# small_analyzer.net
KiCad netlist of a schematic drawn in EAGLE
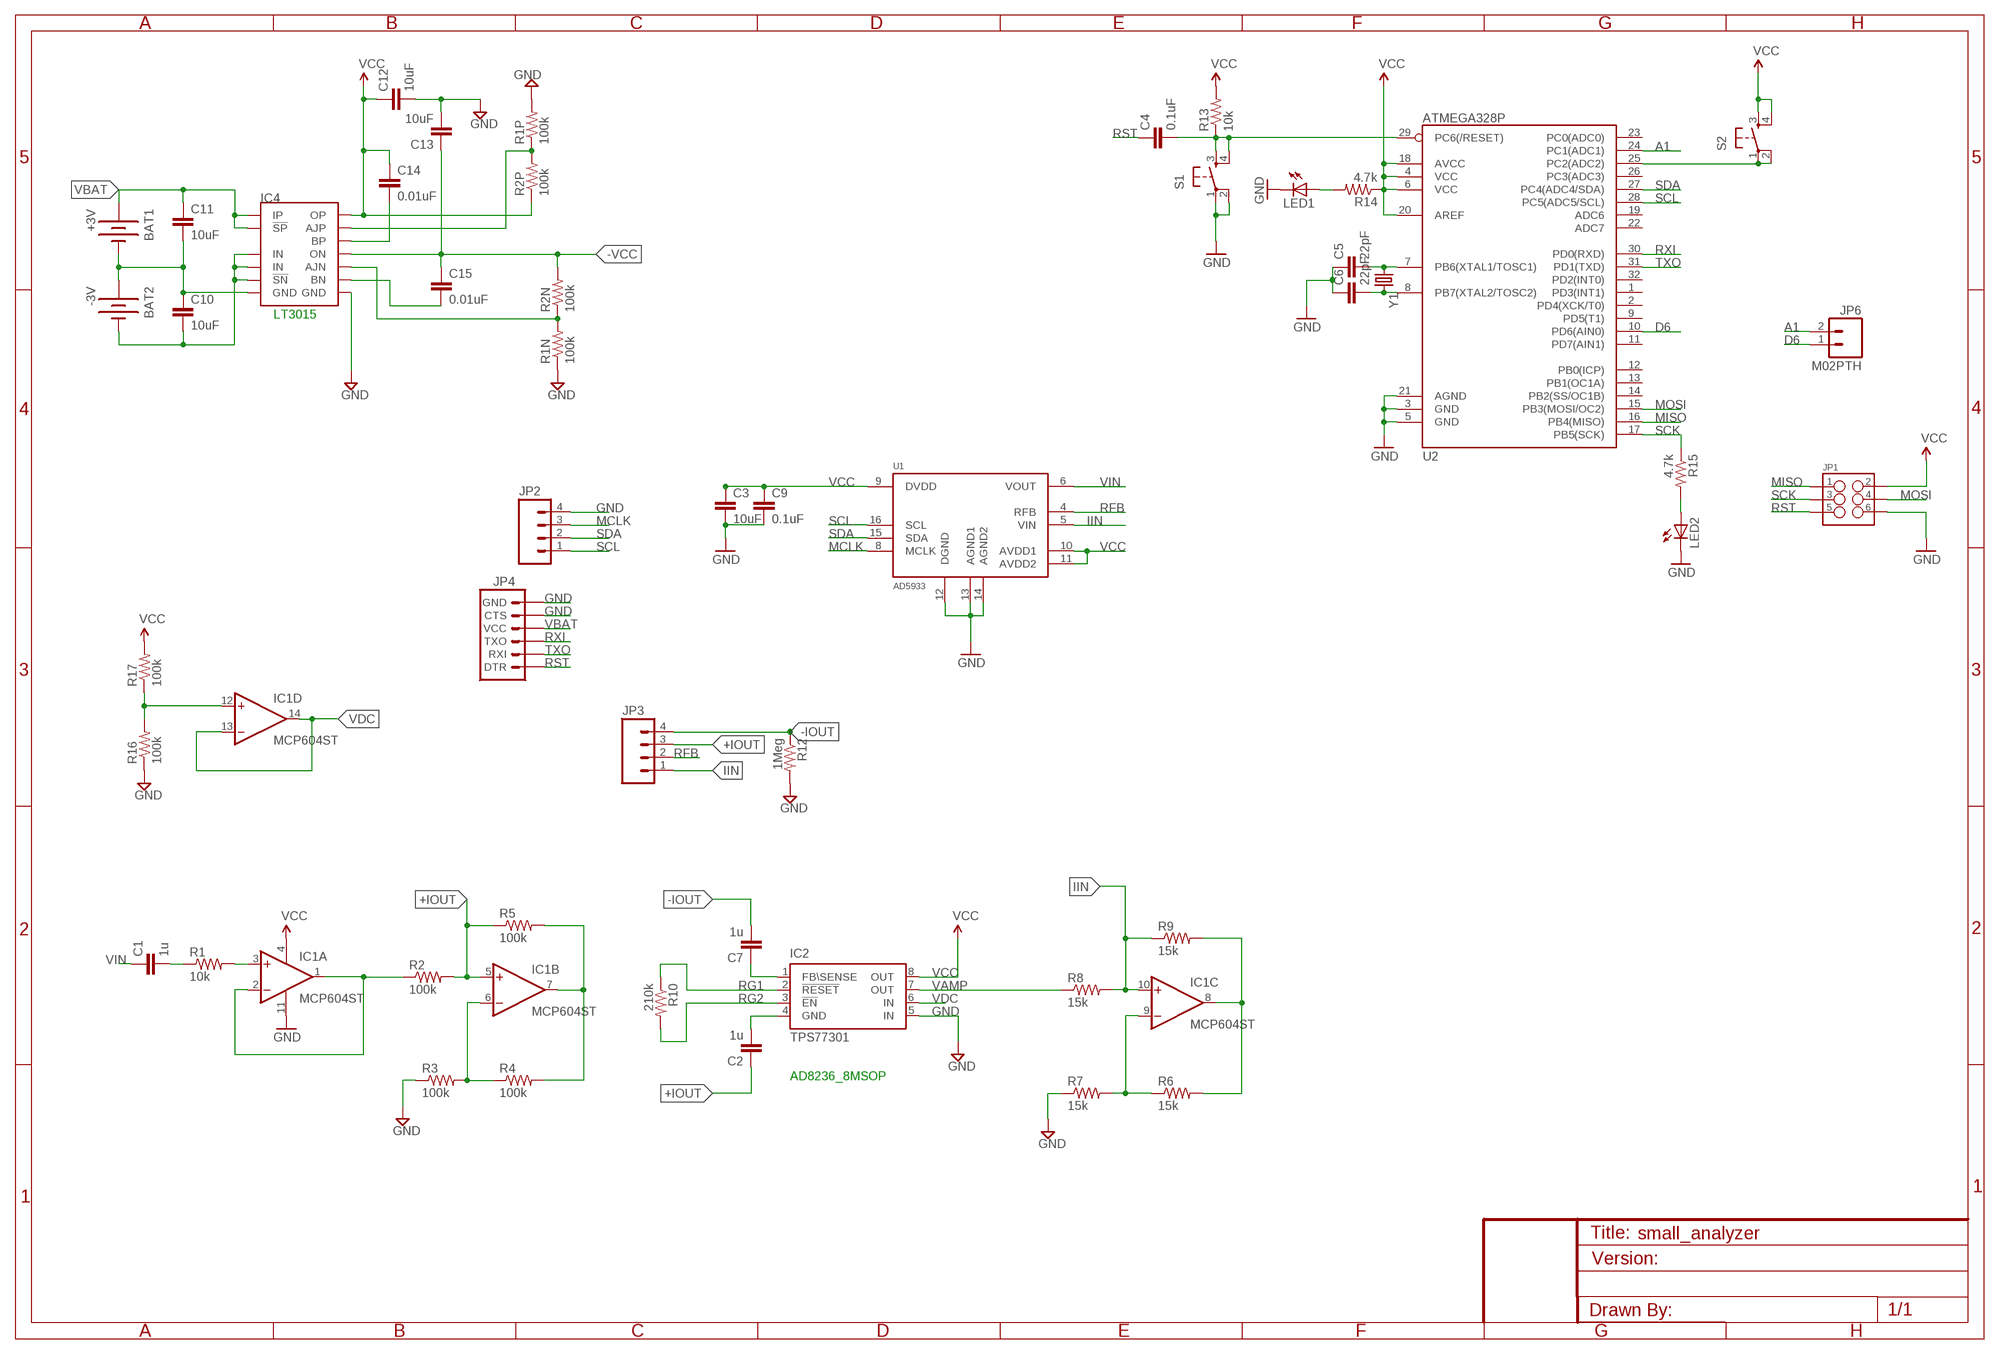
[diagram p0: schematic, sheet 1]

(export (version "E")
  (design (tool "Eeschema 10.0.6"))
  (components
    (comp (ref "BAT1")
      (value "+3V")
      (footprint "eagle-import:BATTCON_12MM")
      (libsource (lib "eagle-import") (part "BATTERY12MM"))
    )
    (comp (ref "BAT2")
      (value "-3V")
      (footprint "eagle-import:BATTCON_12MM")
      (libsource (lib "eagle-import") (part "BATTERY12MM"))
    )
    (comp (ref "C1")
      (value "1u")
      (footprint "eagle-import:0603-CAP")
      (libsource (lib "eagle-import") (part "CAP0603-CAP"))
    )
    (comp (ref "C2")
      (value "1u")
      (footprint "eagle-import:0603-CAP")
      (libsource (lib "eagle-import") (part "CAP0603-CAP"))
    )
    (comp (ref "C3")
      (value "10uF")
      (footprint "eagle-import:0603-CAP")
      (libsource (lib "eagle-import") (part "CAP0603-CAP"))
    )
    (comp (ref "C4")
      (value "0.1uF")
      (footprint "eagle-import:0805")
      (libsource (lib "eagle-import") (part "CAP0805"))
    )
    (comp (ref "C5")
      (value "22pF")
      (footprint "eagle-import:0805")
      (libsource (lib "eagle-import") (part "CAP0805"))
    )
    (comp (ref "C6")
      (value "22pF")
      (footprint "eagle-import:0805")
      (libsource (lib "eagle-import") (part "CAP0805"))
    )
    (comp (ref "C7")
      (value "1u")
      (footprint "eagle-import:0603-CAP")
      (libsource (lib "eagle-import") (part "CAP0603-CAP"))
    )
    (comp (ref "C9")
      (value "0.1uF")
      (footprint "eagle-import:0603-CAP")
      (libsource (lib "eagle-import") (part "CAP0603-CAP"))
    )
    (comp (ref "C10")
      (value "10uF")
      (footprint "eagle-import:0603-CAP")
      (libsource (lib "eagle-import") (part "CAP0603-CAP"))
    )
    (comp (ref "C11")
      (value "10uF")
      (footprint "eagle-import:0603-CAP")
      (libsource (lib "eagle-import") (part "CAP0603-CAP"))
    )
    (comp (ref "C12")
      (value "10uF")
      (footprint "eagle-import:0603-CAP")
      (libsource (lib "eagle-import") (part "CAP0603-CAP"))
    )
    (comp (ref "C13")
      (value "10uF")
      (footprint "eagle-import:0603-CAP")
      (libsource (lib "eagle-import") (part "CAP0603-CAP"))
    )
    (comp (ref "C14")
      (value "0.01uF")
      (footprint "eagle-import:0603-CAP")
      (libsource (lib "eagle-import") (part "CAP0603-CAP"))
    )
    (comp (ref "C15")
      (value "0.01uF")
      (footprint "eagle-import:0603-CAP")
      (libsource (lib "eagle-import") (part "CAP0603-CAP"))
    )
    (comp (ref "IC1")
      (value "MCP604ST")
      (footprint "eagle-import:TSSOP14")
      (libsource (lib "eagle-import") (part "MCP604ST"))
    )
    (comp (ref "IC2")
      (value "TPS77301")
      (footprint "eagle-import:SOP-08")
      (fields (field (name "MF") "TEXAS INSTRUMENT CONNECTORS") (field (name "MPN") "TPS77301DGK"))
      (libsource (lib "eagle-import") (part "TPS77301"))
    )
    (comp (ref "IC4")
      (value "LT3032")
      (footprint "eagle-import:DFN14-4X3DE")
      (libsource (lib "eagle-import") (part "LT3032"))
    )
    (comp (ref "JP1")
      (value "M03X2NO_SILK")
      (footprint "eagle-import:2X3-NS")
      (libsource (lib "eagle-import") (part "M03X2NO_SILK"))
    )
    (comp (ref "JP2")
      (value "M04PTH")
      (footprint "eagle-import:1X04")
      (libsource (lib "eagle-import") (part "M04PTH"))
    )
    (comp (ref "JP3")
      (value "M04PTH")
      (footprint "eagle-import:1X04")
      (libsource (lib "eagle-import") (part "M04PTH"))
    )
    (comp (ref "JP4")
      (value "ARDUINO_SERIAL_PROGRAMLOCK")
      (footprint "eagle-import:1X06_LOCK")
      (libsource (lib "eagle-import") (part "ARDUINO_SERIAL_PROGRAMLOCK"))
    )
    (comp (ref "JP6")
      (value "M02PTH")
      (footprint "eagle-import:1X02")
      (libsource (lib "eagle-import") (part "M02PTH"))
    )
    (comp (ref "LED1")
      (value "LED0603")
      (footprint "eagle-import:LED-0603")
      (libsource (lib "eagle-import") (part "LED0603"))
    )
    (comp (ref "LED2")
      (value "LED0603")
      (footprint "eagle-import:LED-0603")
      (libsource (lib "eagle-import") (part "LED0603"))
    )
    (comp (ref "R1")
      (value "10k")
      (footprint "eagle-import:0603-RES")
      (libsource (lib "eagle-import") (part "RESISTOR0603-RES"))
    )
    (comp (ref "R1N")
      (value "100k")
      (footprint "eagle-import:0805")
      (libsource (lib "eagle-import") (part "RESISTOR0805-RES"))
    )
    (comp (ref "R1P")
      (value "100k")
      (footprint "eagle-import:0805")
      (libsource (lib "eagle-import") (part "RESISTOR0805-RES"))
    )
    (comp (ref "R2")
      (value "100k")
      (footprint "eagle-import:0603-RES")
      (libsource (lib "eagle-import") (part "RESISTOR0603-RES"))
    )
    (comp (ref "R2N")
      (value "100k")
      (footprint "eagle-import:0805")
      (libsource (lib "eagle-import") (part "RESISTOR0805-RES"))
    )
    (comp (ref "R2P")
      (value "100k")
      (footprint "eagle-import:0805")
      (libsource (lib "eagle-import") (part "RESISTOR0805-RES"))
    )
    (comp (ref "R3")
      (value "100k")
      (footprint "eagle-import:0603-RES")
      (libsource (lib "eagle-import") (part "RESISTOR0603-RES"))
    )
    (comp (ref "R4")
      (value "100k")
      (footprint "eagle-import:0603-RES")
      (libsource (lib "eagle-import") (part "RESISTOR0603-RES"))
    )
    (comp (ref "R5")
      (value "100k")
      (footprint "eagle-import:0603-RES")
      (libsource (lib "eagle-import") (part "RESISTOR0603-RES"))
    )
    (comp (ref "R6")
      (value "15k")
      (footprint "eagle-import:0603-RES")
      (libsource (lib "eagle-import") (part "RESISTOR0603-RES"))
    )
    (comp (ref "R7")
      (value "15k")
      (footprint "eagle-import:0603-RES")
      (libsource (lib "eagle-import") (part "RESISTOR0603-RES"))
    )
    (comp (ref "R8")
      (value "15k")
      (footprint "eagle-import:0603-RES")
      (libsource (lib "eagle-import") (part "RESISTOR0603-RES"))
    )
    (comp (ref "R9")
      (value "15k")
      (footprint "eagle-import:0603-RES")
      (libsource (lib "eagle-import") (part "RESISTOR0603-RES"))
    )
    (comp (ref "R10")
      (value "210k")
      (footprint "eagle-import:0603-RES")
      (libsource (lib "eagle-import") (part "RESISTOR0603-RES"))
    )
    (comp (ref "R12")
      (value "1Meg")
      (footprint "eagle-import:0603-RES")
      (libsource (lib "eagle-import") (part "RESISTOR0603-RES"))
    )
    (comp (ref "R13")
      (value "10k")
      (footprint "eagle-import:0805")
      (libsource (lib "eagle-import") (part "RESISTOR0805-RES"))
    )
    (comp (ref "R14")
      (value "4.7k")
      (footprint "eagle-import:0805")
      (libsource (lib "eagle-import") (part "RESISTOR0805-RES"))
    )
    (comp (ref "R15")
      (value "4.7k")
      (footprint "eagle-import:0805")
      (libsource (lib "eagle-import") (part "RESISTOR0805-RES"))
    )
    (comp (ref "R16")
      (value "100k")
      (footprint "eagle-import:0805")
      (libsource (lib "eagle-import") (part "RESISTOR0805-RES"))
    )
    (comp (ref "R17")
      (value "100k")
      (footprint "eagle-import:0805")
      (libsource (lib "eagle-import") (part "RESISTOR0805-RES"))
    )
    (comp (ref "S1")
      (value "TAC_SWITCHSMD")
      (footprint "eagle-import:TACTILE_SWITCH_SMD")
      (libsource (lib "eagle-import") (part "TAC_SWITCHSMD"))
    )
    (comp (ref "S2")
      (value "TAC_SWITCHSMD")
      (footprint "eagle-import:TACTILE_SWITCH_SMD")
      (libsource (lib "eagle-import") (part "TAC_SWITCHSMD"))
    )
    (comp (ref "U1")
      (value "AD5933")
      (footprint "eagle-import:SSOP16")
      (libsource (lib "eagle-import") (part "AD5933"))
    )
    (comp (ref "U2")
      (value "ATMEGA328P")
      (footprint "eagle-import:TQFP32-08")
      (libsource (lib "eagle-import") (part "ATMEGA328_SMT"))
    )
    (comp (ref "Y1")
      (value "CRYSTAL5X3")
      (footprint "eagle-import:CRYSTAL-SMD-5X3")
      (libsource (lib "eagle-import") (part "CRYSTAL5X3"))
    )
  )
  (nets
    (net (code "1") (name "+IOUT") (class "Default")
      (node (ref "C2") (pin "1") (pinfunction "1_1") (pintype "passive"))
      (node (ref "IC1") (pin "5") (pinfunction "+IN_5") (pintype "input"))
      (node (ref "JP3") (pin "3") (pinfunction "3_3") (pintype "passive"))
      (node (ref "R2") (pin "2") (pinfunction "2_2") (pintype "passive"))
      (node (ref "R5") (pin "1") (pinfunction "1_1") (pintype "passive"))
    )
    (net (code "2") (name "-IOUT") (class "Default")
      (node (ref "C7") (pin "2") (pinfunction "2_2") (pintype "passive"))
      (node (ref "JP3") (pin "4") (pinfunction "4_4") (pintype "passive"))
      (node (ref "R12") (pin "1") (pinfunction "1_1") (pintype "passive"))
    )
    (net (code "3") (name "-VCC") (class "Default")
      (node (ref "C13") (pin "1") (pinfunction "1_1") (pintype "passive"))
      (node (ref "C15") (pin "1") (pinfunction "1_1") (pintype "passive"))
      (node (ref "IC4") (pin "7") (pinfunction "ON_7") (pintype "power_in"))
      (node (ref "R2N") (pin "2") (pinfunction "2_2") (pintype "passive"))
    )
    (net (code "4") (name "/A1") (class "Default")
      (node (ref "JP6") (pin "2") (pinfunction "2_2") (pintype "passive"))
      (node (ref "U2") (pin "24") (pinfunction "PC1(ADC1)_24") (pintype "bidirectional"))
    )
    (net (code "5") (name "/D6") (class "Default")
      (node (ref "JP6") (pin "1") (pinfunction "1_1") (pintype "passive"))
      (node (ref "U2") (pin "10") (pinfunction "PD6(AIN0)_10") (pintype "bidirectional"))
    )
    (net (code "6") (name "/MCLK") (class "Default")
      (node (ref "JP2") (pin "3") (pinfunction "3_3") (pintype "passive"))
      (node (ref "U1") (pin "8") (pinfunction "MCLK_8") (pintype "bidirectional"))
    )
    (net (code "7") (name "/MISO") (class "Default")
      (node (ref "JP1") (pin "1") (pinfunction "1_1") (pintype "bidirectional"))
      (node (ref "U2") (pin "16") (pinfunction "PB4(MISO)_16") (pintype "bidirectional"))
    )
    (net (code "8") (name "/MOSI") (class "Default")
      (node (ref "JP1") (pin "4") (pinfunction "4_4") (pintype "bidirectional"))
      (node (ref "U2") (pin "15") (pinfunction "PB3(MOSI/OC2)_15") (pintype "bidirectional"))
    )
    (net (code "9") (name "/RFB") (class "Default")
      (node (ref "JP3") (pin "2") (pinfunction "2_2") (pintype "passive"))
      (node (ref "U1") (pin "4") (pinfunction "RFB_4") (pintype "bidirectional"))
    )
    (net (code "10") (name "/RG1") (class "Default")
      (node (ref "IC2") (pin "2") (pinfunction "~{RESET}_2") (pintype "input"))
      (node (ref "R10") (pin "1") (pinfunction "1_1") (pintype "passive"))
    )
    (net (code "11") (name "/RG2") (class "Default")
      (node (ref "IC2") (pin "3") (pinfunction "~{EN}_3") (pintype "input"))
      (node (ref "R10") (pin "2") (pinfunction "2_2") (pintype "passive"))
    )
    (net (code "12") (name "/RST") (class "Default")
      (node (ref "C4") (pin "1") (pinfunction "1_1") (pintype "passive"))
      (node (ref "JP1") (pin "5") (pinfunction "5_5") (pintype "bidirectional"))
      (node (ref "JP4") (pin "1") (pinfunction "DTR_1") (pintype "passive"))
    )
    (net (code "13") (name "/RXI") (class "Default")
      (node (ref "JP4") (pin "3") (pinfunction "TXO_3") (pintype "passive"))
      (node (ref "U2") (pin "30") (pinfunction "PD0(RXD)_30") (pintype "bidirectional"))
    )
    (net (code "14") (name "/SCK") (class "Default")
      (node (ref "JP1") (pin "3") (pinfunction "3_3") (pintype "bidirectional"))
      (node (ref "R15") (pin "1") (pinfunction "1_1") (pintype "passive"))
      (node (ref "U2") (pin "17") (pinfunction "PB5(SCK)_17") (pintype "bidirectional"))
    )
    (net (code "15") (name "/SCL") (class "Default")
      (node (ref "JP2") (pin "1") (pinfunction "1_1") (pintype "passive"))
      (node (ref "U1") (pin "16") (pinfunction "SCL_16") (pintype "bidirectional"))
      (node (ref "U2") (pin "28") (pinfunction "PC5(ADC5/SCL)_28") (pintype "bidirectional"))
    )
    (net (code "16") (name "/SDA") (class "Default")
      (node (ref "JP2") (pin "2") (pinfunction "2_2") (pintype "passive"))
      (node (ref "U1") (pin "15") (pinfunction "SDA_15") (pintype "bidirectional"))
      (node (ref "U2") (pin "27") (pinfunction "PC4(ADC4/SDA)_27") (pintype "bidirectional"))
    )
    (net (code "17") (name "/TXO") (class "Default")
      (node (ref "JP4") (pin "2") (pinfunction "RXI_2") (pintype "passive"))
      (node (ref "U2") (pin "31") (pinfunction "PD1(TXD)_31") (pintype "bidirectional"))
    )
    (net (code "18") (name "/VAMP") (class "Default")
      (node (ref "IC2") (pin "7") (pinfunction "OUT_7") (pintype "output"))
      (node (ref "R8") (pin "1") (pinfunction "1_1") (pintype "passive"))
    )
    (net (code "19") (name "/VIN") (class "Default")
      (node (ref "C1") (pin "1") (pinfunction "1_1") (pintype "passive"))
      (node (ref "U1") (pin "6") (pinfunction "VOUT_6") (pintype "bidirectional"))
    )
    (net (code "20") (name "GND") (class "Default")
      (node (ref "C12") (pin "2") (pinfunction "2_2") (pintype "passive"))
      (node (ref "C13") (pin "2") (pinfunction "2_2") (pintype "passive"))
      (node (ref "C3") (pin "2") (pinfunction "2_2") (pintype "passive"))
      (node (ref "C5") (pin "1") (pinfunction "1_1") (pintype "passive"))
      (node (ref "C6") (pin "1") (pinfunction "1_1") (pintype "passive"))
      (node (ref "C9") (pin "2") (pinfunction "2_2") (pintype "passive"))
      (node (ref "IC1") (pin "11") (pinfunction "V-_11") (pintype "power_in"))
      (node (ref "IC2") (pin "5") (pinfunction "IN_5") (pintype "input"))
      (node (ref "IC4") (pin "5") (pinfunction "GND_5") (pintype "power_in"))
      (node (ref "JP1") (pin "6") (pinfunction "6_6") (pintype "bidirectional"))
      (node (ref "JP2") (pin "4") (pinfunction "4_4") (pintype "passive"))
      (node (ref "JP4") (pin "5") (pinfunction "CTS_5") (pintype "passive"))
      (node (ref "JP4") (pin "6") (pinfunction "GND_6") (pintype "passive"))
      (node (ref "LED1") (pin "C") (pinfunction "C_C") (pintype "passive"))
      (node (ref "LED2") (pin "C") (pinfunction "C_C") (pintype "passive"))
      (node (ref "R12") (pin "2") (pinfunction "2_2") (pintype "passive"))
      (node (ref "R16") (pin "1") (pinfunction "1_1") (pintype "passive"))
      (node (ref "R1N") (pin "1") (pinfunction "1_1") (pintype "passive"))
      (node (ref "R1P") (pin "2") (pinfunction "2_2") (pintype "passive"))
      (node (ref "R3") (pin "1") (pinfunction "1_1") (pintype "passive"))
      (node (ref "R7") (pin "1") (pinfunction "1_1") (pintype "passive"))
      (node (ref "S1") (pin "1") (pinfunction "1_1") (pintype "passive"))
      (node (ref "S1") (pin "2") (pinfunction "2_2") (pintype "passive"))
      (node (ref "U1") (pin "12") (pinfunction "DGND_12") (pintype "bidirectional"))
      (node (ref "U1") (pin "13") (pinfunction "AGND1_13") (pintype "bidirectional"))
      (node (ref "U1") (pin "14") (pinfunction "AGND2_14") (pintype "bidirectional"))
      (node (ref "U2") (pin "21") (pinfunction "AGND_21") (pintype "bidirectional"))
      (node (ref "U2") (pin "3") (pinfunction "GND_3") (pintype "bidirectional"))
      (node (ref "U2") (pin "5") (pinfunction "GND_5") (pintype "bidirectional"))
    )
    (net (code "21") (name "IIN") (class "Default")
      (node (ref "IC1") (pin "10") (pinfunction "+IN_10") (pintype "input"))
      (node (ref "JP3") (pin "1") (pinfunction "1_1") (pintype "passive"))
      (node (ref "R8") (pin "2") (pinfunction "2_2") (pintype "passive"))
      (node (ref "R9") (pin "1") (pinfunction "1_1") (pintype "passive"))
      (node (ref "U1") (pin "5") (pinfunction "VIN_5") (pintype "bidirectional"))
    )
    (net (code "22") (name "Net-(BAT1--)") (class "Default")
      (node (ref "BAT1") (pin "GND") (pinfunction "-_GND") (pintype "power_in"))
      (node (ref "BAT2") (pin "PWR@1") (pinfunction "+_PWR@1") (pintype "power_in"))
      (node (ref "C10") (pin "1") (pinfunction "1_1") (pintype "passive"))
      (node (ref "C11") (pin "2") (pinfunction "2_2") (pintype "passive"))
      (node (ref "IC4") (pin "4") (pinfunction "GND_4") (pintype "power_in"))
    )
    (net (code "23") (name "Net-(BAT2--)") (class "Default")
      (node (ref "BAT2") (pin "GND") (pinfunction "-_GND") (pintype "power_in"))
      (node (ref "C10") (pin "2") (pinfunction "2_2") (pintype "passive"))
      (node (ref "IC4") (pin "10") (pinfunction "~{SN}_10") (pintype "bidirectional"))
      (node (ref "IC4") (pin "6") (pinfunction "IN_6") (pintype "power_in"))
      (node (ref "IC4") (pin "9") (pinfunction "IN_9") (pintype "power_in"))
    )
    (net (code "24") (name "Net-(C1-Pad2)") (class "Default")
      (node (ref "C1") (pin "2") (pinfunction "2_2") (pintype "passive"))
      (node (ref "R1") (pin "1") (pinfunction "1_1") (pintype "passive"))
    )
    (net (code "25") (name "Net-(IC1A-+IN)") (class "Default")
      (node (ref "IC1") (pin "3") (pinfunction "+IN_3") (pintype "input"))
      (node (ref "R1") (pin "2") (pinfunction "2_2") (pintype "passive"))
    )
    (net (code "26") (name "Net-(IC1A--IN)") (class "Default")
      (node (ref "IC1") (pin "1") (pinfunction "OUT_1") (pintype "output"))
      (node (ref "IC1") (pin "2") (pinfunction "-IN_2") (pintype "input"))
      (node (ref "R2") (pin "1") (pinfunction "1_1") (pintype "passive"))
    )
    (net (code "27") (name "Net-(IC1B--IN)") (class "Default")
      (node (ref "IC1") (pin "6") (pinfunction "-IN_6") (pintype "input"))
      (node (ref "R3") (pin "2") (pinfunction "2_2") (pintype "passive"))
      (node (ref "R4") (pin "1") (pinfunction "1_1") (pintype "passive"))
    )
    (net (code "28") (name "Net-(IC1B-OUT)") (class "Default")
      (node (ref "IC1") (pin "7") (pinfunction "OUT_7") (pintype "output"))
      (node (ref "R4") (pin "2") (pinfunction "2_2") (pintype "passive"))
      (node (ref "R5") (pin "2") (pinfunction "2_2") (pintype "passive"))
    )
    (net (code "29") (name "Net-(IC1C--IN)") (class "Default")
      (node (ref "IC1") (pin "9") (pinfunction "-IN_9") (pintype "input"))
      (node (ref "R6") (pin "1") (pinfunction "1_1") (pintype "passive"))
      (node (ref "R7") (pin "2") (pinfunction "2_2") (pintype "passive"))
    )
    (net (code "30") (name "Net-(IC1C-OUT)") (class "Default")
      (node (ref "IC1") (pin "8") (pinfunction "OUT_8") (pintype "output"))
      (node (ref "R6") (pin "2") (pinfunction "2_2") (pintype "passive"))
      (node (ref "R9") (pin "2") (pinfunction "2_2") (pintype "passive"))
    )
    (net (code "31") (name "Net-(IC1D-+IN)") (class "Default")
      (node (ref "IC1") (pin "12") (pinfunction "+IN_12") (pintype "input"))
      (node (ref "R16") (pin "2") (pinfunction "2_2") (pintype "passive"))
      (node (ref "R17") (pin "1") (pinfunction "1_1") (pintype "passive"))
    )
    (net (code "32") (name "Net-(IC2-FB\\SENSE)") (class "Default")
      (node (ref "C7") (pin "1") (pinfunction "1_1") (pintype "passive"))
      (node (ref "IC2") (pin "1") (pinfunction "FB\\SENSE_1") (pintype "input"))
    )
    (net (code "33") (name "Net-(IC2-GND)") (class "Default")
      (node (ref "C2") (pin "2") (pinfunction "2_2") (pintype "passive"))
      (node (ref "IC2") (pin "4") (pinfunction "GND_4") (pintype "power_in"))
    )
    (net (code "34") (name "Net-(IC4-AJN)") (class "Default")
      (node (ref "IC4") (pin "8") (pinfunction "AJN_8") (pintype "bidirectional"))
      (node (ref "R1N") (pin "2") (pinfunction "2_2") (pintype "passive"))
      (node (ref "R2N") (pin "1") (pinfunction "1_1") (pintype "passive"))
    )
    (net (code "35") (name "Net-(IC4-AJP)") (class "Default")
      (node (ref "IC4") (pin "2") (pinfunction "AJP_2") (pintype "bidirectional"))
      (node (ref "R1P") (pin "1") (pinfunction "1_1") (pintype "passive"))
      (node (ref "R2P") (pin "2") (pinfunction "2_2") (pintype "passive"))
    )
    (net (code "36") (name "Net-(IC4-BN)") (class "Default")
      (node (ref "C15") (pin "2") (pinfunction "2_2") (pintype "passive"))
      (node (ref "IC4") (pin "11") (pinfunction "BN_11") (pintype "bidirectional"))
    )
    (net (code "37") (name "Net-(IC4-BP)") (class "Default")
      (node (ref "C14") (pin "2") (pinfunction "2_2") (pintype "passive"))
      (node (ref "IC4") (pin "3") (pinfunction "BP_3") (pintype "bidirectional"))
    )
    (net (code "38") (name "Net-(LED1-PadA)") (class "Default")
      (node (ref "LED1") (pin "A") (pinfunction "A_A") (pintype "passive"))
      (node (ref "R14") (pin "2") (pinfunction "2_2") (pintype "passive"))
    )
    (net (code "39") (name "Net-(LED2-PadA)") (class "Default")
      (node (ref "LED2") (pin "A") (pinfunction "A_A") (pintype "passive"))
      (node (ref "R15") (pin "2") (pinfunction "2_2") (pintype "passive"))
    )
    (net (code "40") (name "Net-(U2-PB6(XTAL1{slash}TOSC1))") (class "Default")
      (node (ref "C5") (pin "2") (pinfunction "2_2") (pintype "passive"))
      (node (ref "U2") (pin "7") (pinfunction "PB6(XTAL1/TOSC1)_7") (pintype "bidirectional"))
      (node (ref "Y1") (pin "1") (pinfunction "1_1") (pintype "passive"))
    )
    (net (code "41") (name "Net-(U2-PB7(XTAL2{slash}TOSC2))") (class "Default")
      (node (ref "C6") (pin "2") (pinfunction "2_2") (pintype "passive"))
      (node (ref "U2") (pin "8") (pinfunction "PB7(XTAL2/TOSC2)_8") (pintype "bidirectional"))
      (node (ref "Y1") (pin "3") (pinfunction "2_3") (pintype "passive"))
    )
    (net (code "42") (name "Net-(U2-PC2(ADC2))") (class "Default")
      (node (ref "S2") (pin "1") (pinfunction "1_1") (pintype "passive"))
      (node (ref "S2") (pin "2") (pinfunction "2_2") (pintype "passive"))
      (node (ref "U2") (pin "25") (pinfunction "PC2(ADC2)_25") (pintype "bidirectional"))
    )
    (net (code "43") (name "Net-(U2-PC6({slash}RESET))") (class "Default")
      (node (ref "C4") (pin "2") (pinfunction "2_2") (pintype "passive"))
      (node (ref "R13") (pin "1") (pinfunction "1_1") (pintype "passive"))
      (node (ref "S1") (pin "3") (pinfunction "3_3") (pintype "passive"))
      (node (ref "S1") (pin "4") (pinfunction "4_4") (pintype "passive"))
      (node (ref "U2") (pin "29") (pinfunction "PC6(/RESET)_29") (pintype "bidirectional"))
    )
    (net (code "44") (name "VBAT") (class "Default")
      (node (ref "BAT1") (pin "PWR@1") (pinfunction "+_PWR@1") (pintype "power_in"))
      (node (ref "C11") (pin "1") (pinfunction "1_1") (pintype "passive"))
      (node (ref "IC4") (pin "12") (pinfunction "~{SP}_12") (pintype "bidirectional"))
      (node (ref "IC4") (pin "14") (pinfunction "IP_14") (pintype "power_in"))
      (node (ref "JP4") (pin "4") (pinfunction "VCC_4") (pintype "passive"))
    )
    (net (code "45") (name "VCC") (class "Default")
      (node (ref "C12") (pin "1") (pinfunction "1_1") (pintype "passive"))
      (node (ref "C14") (pin "1") (pinfunction "1_1") (pintype "passive"))
      (node (ref "C3") (pin "1") (pinfunction "1_1") (pintype "passive"))
      (node (ref "C9") (pin "1") (pinfunction "1_1") (pintype "passive"))
      (node (ref "IC1") (pin "4") (pinfunction "V+_4") (pintype "power_in"))
      (node (ref "IC2") (pin "8") (pinfunction "OUT_8") (pintype "passive"))
      (node (ref "IC4") (pin "1") (pinfunction "OP_1") (pintype "power_in"))
      (node (ref "JP1") (pin "2") (pinfunction "2_2") (pintype "bidirectional"))
      (node (ref "R13") (pin "2") (pinfunction "2_2") (pintype "passive"))
      (node (ref "R14") (pin "1") (pinfunction "1_1") (pintype "passive"))
      (node (ref "R17") (pin "2") (pinfunction "2_2") (pintype "passive"))
      (node (ref "R2P") (pin "1") (pinfunction "1_1") (pintype "passive"))
      (node (ref "S2") (pin "3") (pinfunction "3_3") (pintype "passive"))
      (node (ref "S2") (pin "4") (pinfunction "4_4") (pintype "passive"))
      (node (ref "U1") (pin "10") (pinfunction "AVDD1_10") (pintype "bidirectional"))
      (node (ref "U1") (pin "11") (pinfunction "AVDD2_11") (pintype "bidirectional"))
      (node (ref "U1") (pin "9") (pinfunction "DVDD_9") (pintype "bidirectional"))
      (node (ref "U2") (pin "18") (pinfunction "AVCC_18") (pintype "bidirectional"))
      (node (ref "U2") (pin "20") (pinfunction "AREF_20") (pintype "bidirectional"))
      (node (ref "U2") (pin "4") (pinfunction "VCC_4") (pintype "bidirectional"))
      (node (ref "U2") (pin "6") (pinfunction "VCC_6") (pintype "bidirectional"))
    )
    (net (code "46") (name "VDC") (class "Default")
      (node (ref "IC1") (pin "13") (pinfunction "-IN_13") (pintype "input"))
      (node (ref "IC1") (pin "14") (pinfunction "OUT_14") (pintype "output"))
      (node (ref "IC2") (pin "6") (pinfunction "IN_6") (pintype "input"))
    )
    (net (code "47") (name "unconnected-(U2-ADC6-Pad19)") (class "Default")
      (node (ref "U2") (pin "19") (pinfunction "ADC6_19") (pintype "bidirectional"))
    )
    (net (code "48") (name "unconnected-(U2-ADC7-Pad22)") (class "Default")
      (node (ref "U2") (pin "22") (pinfunction "ADC7_22") (pintype "bidirectional"))
    )
    (net (code "49") (name "unconnected-(U2-PB0(ICP)-Pad12)") (class "Default")
      (node (ref "U2") (pin "12") (pinfunction "PB0(ICP)_12") (pintype "bidirectional"))
    )
    (net (code "50") (name "unconnected-(U2-PB1(OC1A)-Pad13)") (class "Default")
      (node (ref "U2") (pin "13") (pinfunction "PB1(OC1A)_13") (pintype "bidirectional"))
    )
    (net (code "51") (name "unconnected-(U2-PB2(SS{slash}OC1B)-Pad14)") (class "Default")
      (node (ref "U2") (pin "14") (pinfunction "PB2(SS/OC1B)_14") (pintype "bidirectional"))
    )
    (net (code "52") (name "unconnected-(U2-PC0(ADC0)-Pad23)") (class "Default")
      (node (ref "U2") (pin "23") (pinfunction "PC0(ADC0)_23") (pintype "bidirectional"))
    )
    (net (code "53") (name "unconnected-(U2-PC3(ADC3)-Pad26)") (class "Default")
      (node (ref "U2") (pin "26") (pinfunction "PC3(ADC3)_26") (pintype "bidirectional"))
    )
    (net (code "54") (name "unconnected-(U2-PD2(INT0)-Pad32)") (class "Default")
      (node (ref "U2") (pin "32") (pinfunction "PD2(INT0)_32") (pintype "bidirectional"))
    )
    (net (code "55") (name "unconnected-(U2-PD3(INT1)-Pad1)") (class "Default")
      (node (ref "U2") (pin "1") (pinfunction "PD3(INT1)_1") (pintype "bidirectional"))
    )
    (net (code "56") (name "unconnected-(U2-PD4(XCK{slash}T0)-Pad2)") (class "Default")
      (node (ref "U2") (pin "2") (pinfunction "PD4(XCK/T0)_2") (pintype "bidirectional"))
    )
    (net (code "57") (name "unconnected-(U2-PD5(T1)-Pad9)") (class "Default")
      (node (ref "U2") (pin "9") (pinfunction "PD5(T1)_9") (pintype "bidirectional"))
    )
    (net (code "58") (name "unconnected-(U2-PD7(AIN1)-Pad11)") (class "Default")
      (node (ref "U2") (pin "11") (pinfunction "PD7(AIN1)_11") (pintype "bidirectional"))
    )
  )
)
